# Gain.net
KiCad netlist of a schematic drawn in Altium Designer
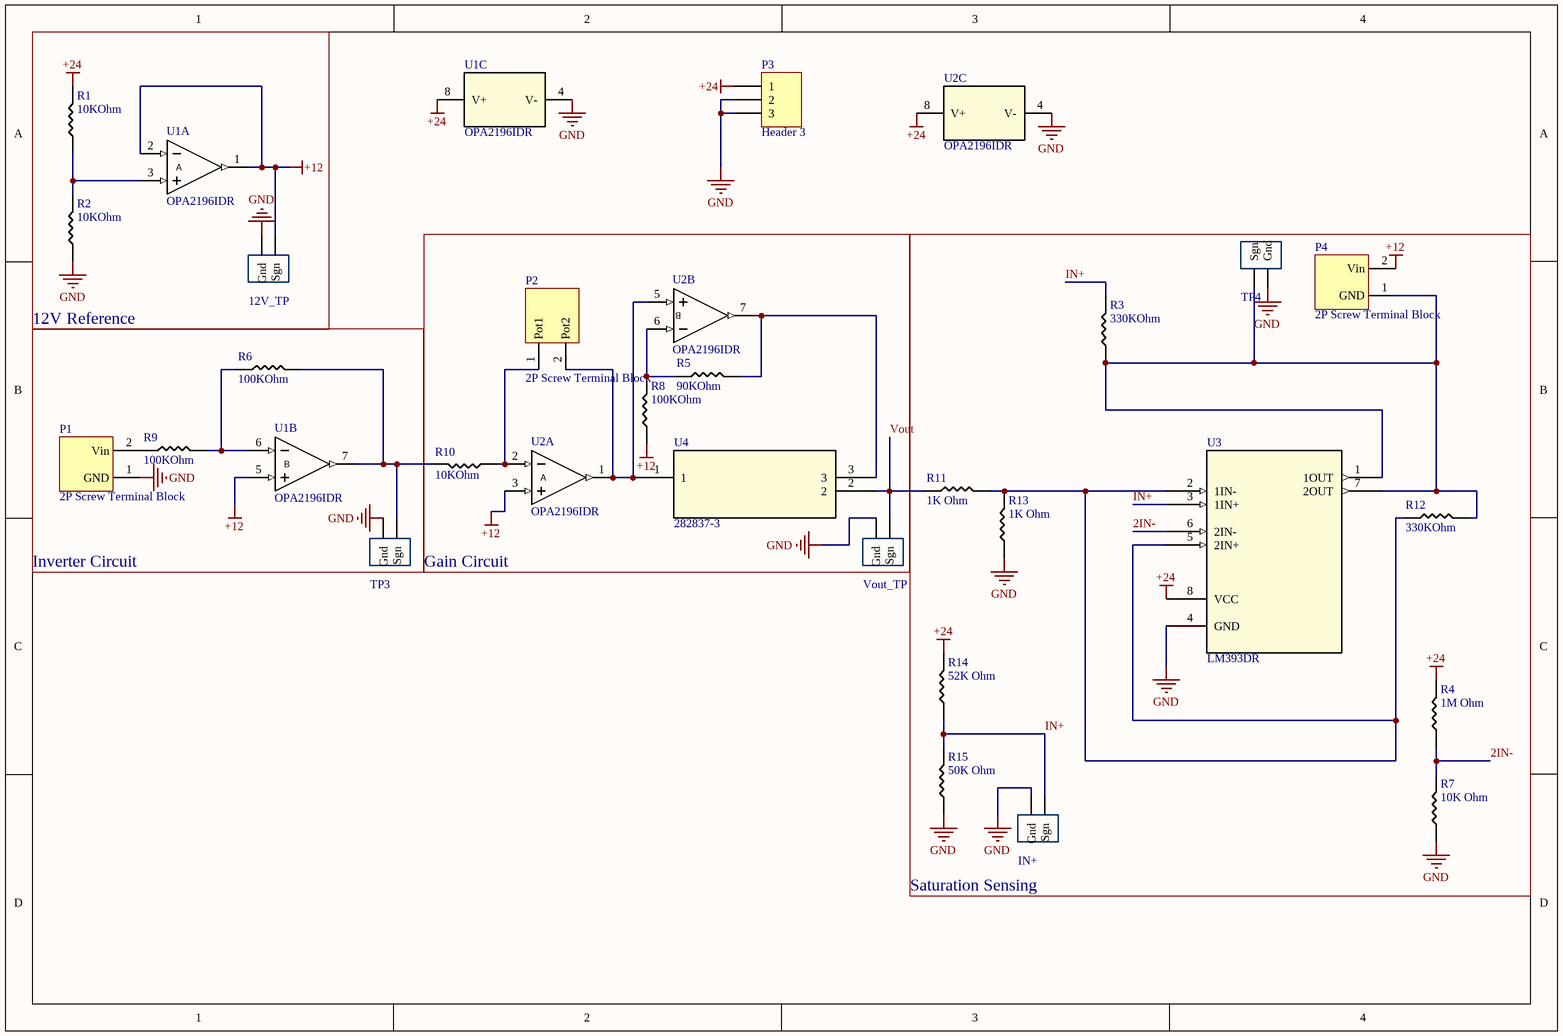
[diagram p0: Gain.SchDoc]

(export (version "E")
  (design (tool "Eeschema 10.0.6"))
  (components
    (comp (ref "12V_TP")
      (value "10x Probe TP")
      (footprint "TP10x_Probe")
      (description "Test Point 300 mil centers")
      (libsource (lib "") (part "TP_10x_Probe_1"))
    )
    (comp (ref "IN+")
      (value "10x Probe TP")
      (footprint "TP10x_Probe")
      (description "Test Point 300 mil centers")
      (libsource (lib "") (part "TP_10x_Probe_1"))
    )
    (comp (ref "P1")
      (value "2P Screw Terminal Block")
      (footprint "P_Terminal block 3.5mm-pitch")
      (description "Green Straight pin 3.5mm  pitch; P=3.5mm  Screw terminal ROHS")
      (fields (field (name "MFR PART #") "KF350-3.5-2P") (field (name "MANUFACTURER") "Cixi Kefa Elec"))
      (libsource (lib "") (part "P_Terminal block_1"))
    )
    (comp (ref "P2")
      (value "2P Screw Terminal Block")
      (footprint "P_Terminal block 3.5mm-pitch")
      (description "Green Straight pin 3.5mm  pitch; P=3.5mm  Screw terminal ROHS")
      (fields (field (name "MFR PART #") "KF350-3.5-2P") (field (name "MANUFACTURER") "Cixi Kefa Elec"))
      (libsource (lib "ECEN5730Lib_2023_05_DS") (part "P_Terminal block"))
    )
    (comp (ref "P3")
      (value "Header 3")
      (footprint "HDR1X3")
      (description "Header, 3-Pin")
      (fields (field (name "PUBLISHER") "Altium Limited"))
      (libsource (lib "Miscellaneous Connectors") (part "Header 3"))
    )
    (comp (ref "P4")
      (value "2P Screw Terminal Block")
      (footprint "P_Terminal block 3.5mm-pitch")
      (description "Green Straight pin 3.5mm  pitch; P=3.5mm  Screw terminal ROHS")
      (fields (field (name "MFR PART #") "KF350-3.5-2P") (field (name "MANUFACTURER") "Cixi Kefa Elec"))
      (libsource (lib "") (part "P_Terminal block_1"))
    )
    (comp (ref "R1")
      (value "10KOhm")
      (footprint "1206_Passive_Resitor")
      (description "10 kOhms ±5% 0.25W, 1/4W Chip Resistor 1206 (3216 Metric) Automotive AEC-Q200 Thick Film")
      (fields (field (name "MFR PART #") "RMCF1206FT10K0") (field (name "LCSC PART#") "C17902"))
      (libsource (lib "ECEN5730Lib_2023_05_DS") (part "R_10KOhm_1206"))
    )
    (comp (ref "R2")
      (value "10KOhm")
      (footprint "1206_Passive_Resitor")
      (description "10 kOhms ±5% 0.25W, 1/4W Chip Resistor 1206 (3216 Metric) Automotive AEC-Q200 Thick Film")
      (fields (field (name "MFR PART #") "RMCF1206FT10K0") (field (name "LCSC PART#") "C17902"))
      (libsource (lib "ECEN5730Lib_2023_05_DS") (part "R_10KOhm_1206"))
    )
    (comp (ref "R3")
      (value "330KOhm")
      (footprint "1206_Passive_Resitor")
      (description "CHIP RESISTOR - SURFACE MOUNT 300OHMS ±1% 1/4W 1206 ROHS")
      (fields (field (name "MFR PART #") "1206W4F3000T5E") (field (name "LCSC PART#") "C17887"))
      (libsource (lib "ECEN5730Lib_2023_05_DS") (part "R_300Ohm_1206"))
    )
    (comp (ref "R4")
      (value "1M Ohm")
      (footprint "1206_Passive_Resitor")
      (description "CHIP RESISTOR - SURFACE MOUNT 1KOHMS ±1% 1/4W 1206 ROHS")
      (fields (field (name "MFR PART #") "RNCP1206FTD1K00CT") (field (name "LCSC PART#") "C4410"))
      (libsource (lib "ECEN5730Lib_2023_05_DS") (part "R_1K_1206"))
    )
    (comp (ref "R5")
      (value "90KOhm")
      (footprint "1206_Passive_Resitor")
      (description "100kΩ ±1% 0.25W ±100ppm/℃ 1206 Chip Resistor - Surface Mount RoHS")
      (fields (field (name "LCSC PART#") "C17900") (field (name "MFR PART #") "1206W4F1003T5E"))
      (libsource (lib "ECEN5730Lib_2023_05_DS") (part "R_100KOhm_1206"))
    )
    (comp (ref "R6")
      (value "100KOhm")
      (footprint "1206_Passive_Resitor")
      (description "100kΩ ±1% 0.25W ±100ppm/℃ 1206 Chip Resistor - Surface Mount RoHS")
      (fields (field (name "LCSC PART#") "C17900") (field (name "MFR PART #") "1206W4F1003T5E"))
      (libsource (lib "ECEN5730Lib_2023_05_DS") (part "R_100KOhm_1206"))
    )
    (comp (ref "R7")
      (value "10K Ohm")
      (footprint "1206_Passive_Resitor")
      (description "CHIP RESISTOR - SURFACE MOUNT 1KOHMS ±1% 1/4W 1206 ROHS")
      (fields (field (name "MFR PART #") "RNCP1206FTD1K00CT") (field (name "LCSC PART#") "C4410"))
      (libsource (lib "ECEN5730Lib_2023_05_DS") (part "R_1K_1206"))
    )
    (comp (ref "R8")
      (value "100KOhm")
      (footprint "1206_Passive_Resitor")
      (description "100kΩ ±1% 0.25W ±100ppm/℃ 1206 Chip Resistor - Surface Mount RoHS")
      (fields (field (name "LCSC PART#") "C17900") (field (name "MFR PART #") "1206W4F1003T5E"))
      (libsource (lib "ECEN5730Lib_2023_05_DS") (part "R_100KOhm_1206"))
    )
    (comp (ref "R9")
      (value "100KOhm")
      (footprint "1206_Passive_Resitor")
      (description "100kΩ ±1% 0.25W ±100ppm/℃ 1206 Chip Resistor - Surface Mount RoHS")
      (fields (field (name "LCSC PART#") "C17900") (field (name "MFR PART #") "1206W4F1003T5E"))
      (libsource (lib "ECEN5730Lib_2023_05_DS") (part "R_100KOhm_1206"))
    )
    (comp (ref "R10")
      (value "10KOhm")
      (footprint "1206_Passive_Resitor")
      (description "10 kOhms ±5% 0.25W, 1/4W Chip Resistor 1206 (3216 Metric) Automotive AEC-Q200 Thick Film")
      (fields (field (name "MFR PART #") "RMCF1206FT10K0") (field (name "LCSC PART#") "C17902"))
      (libsource (lib "ECEN5730Lib_2023_05_DS") (part "R_10KOhm_1206"))
    )
    (comp (ref "R11")
      (value "1K Ohm")
      (footprint "1206_Passive_Resitor")
      (description "CHIP RESISTOR - SURFACE MOUNT 1KOHMS ±1% 1/4W 1206 ROHS")
      (fields (field (name "MFR PART #") "RNCP1206FTD1K00CT") (field (name "LCSC PART#") "C4410"))
      (libsource (lib "ECEN5730Lib_2023_05_DS") (part "R_1K_1206"))
    )
    (comp (ref "R12")
      (value "330KOhm")
      (footprint "1206_Passive_Resitor")
      (description "CHIP RESISTOR - SURFACE MOUNT 300OHMS ±1% 1/4W 1206 ROHS")
      (fields (field (name "MFR PART #") "1206W4F3000T5E") (field (name "LCSC PART#") "C17887"))
      (libsource (lib "ECEN5730Lib_2023_05_DS") (part "R_300Ohm_1206"))
    )
    (comp (ref "R13")
      (value "1K Ohm")
      (footprint "1206_Passive_Resitor")
      (description "CHIP RESISTOR - SURFACE MOUNT 1KOHMS ±1% 1/4W 1206 ROHS")
      (fields (field (name "MFR PART #") "RNCP1206FTD1K00CT") (field (name "LCSC PART#") "C4410"))
      (libsource (lib "ECEN5730Lib_2023_05_DS") (part "R_1K_1206"))
    )
    (comp (ref "R14")
      (value "52K Ohm")
      (footprint "1206_Passive_Resitor")
      (description "CHIP RESISTOR - SURFACE MOUNT 1KOHMS ±1% 1/4W 1206 ROHS")
      (fields (field (name "MFR PART #") "RNCP1206FTD1K00CT") (field (name "LCSC PART#") "C4410"))
      (libsource (lib "ECEN5730Lib_2023_05_DS") (part "R_1K_1206"))
    )
    (comp (ref "R15")
      (value "50K Ohm")
      (footprint "1206_Passive_Resitor")
      (description "CHIP RESISTOR - SURFACE MOUNT 1KOHMS ±1% 1/4W 1206 ROHS")
      (fields (field (name "MFR PART #") "RNCP1206FTD1K00CT") (field (name "LCSC PART#") "C4410"))
      (libsource (lib "ECEN5730Lib_2023_05_DS") (part "R_1K_1206"))
    )
    (comp (ref "TP3")
      (value "10x Probe TP")
      (footprint "TP10x_Probe")
      (description "Test Point 300 mil centers")
      (libsource (lib "") (part "TP_10x_Probe_1"))
    )
    (comp (ref "TP4")
      (value "10x Probe TP")
      (footprint "TP10x_Probe")
      (description "Test Point 300 mil centers")
      (libsource (lib "ECEN5730Lib_2023_05_DS") (part "TP_10x_Probe"))
    )
    (comp (ref "U1")
      (value "OPA2196IDR")
      (footprint "D0008A_N")
      (description "Dual, 36-V, low power, all-purpose amplifier with mux-friendly input 8-SOIC -40 to 125")
      (fields (field (name "COPYRIGHT") "Copyright (C) 2026 Ultra Librarian. All rights reserved."))
      (libsource (lib "Integrated_Library1") (part "OPA2196IDR"))
    )
    (comp (ref "U2")
      (value "OPA2196IDR")
      (footprint "D0008A_N")
      (description "Dual, 36-V, low power, all-purpose amplifier with mux-friendly input 8-SOIC -40 to 125")
      (fields (field (name "COPYRIGHT") "Copyright (C) 2026 Ultra Librarian. All rights reserved."))
      (libsource (lib "") (part "OPA2196IDR_1"))
    )
    (comp (ref "U3")
      (value "LM393DR")
      (footprint "D8")
      (description "Dual differential comparator, commercial grade 8-SOIC 0 to 70")
      (fields (field (name "COPYRIGHT") "Copyright (C) 2025 Ultra Librarian. All rights reserved."))
      (libsource (lib "LM393DR") (part "LM393DR"))
    )
    (comp (ref "U4")
      (value "282837-3")
      (footprint "282837-3_TYC")
      (description "TERMI-BLOK PCB MOUNT 3P")
      (fields (field (name "COPYRIGHT") "Copyright (C) 2025 Ultra Librarian. All rights reserved."))
      (libsource (lib "282837-3") (part "282837-3"))
    )
    (comp (ref "Vout_TP")
      (value "10x Probe TP")
      (footprint "TP10x_Probe")
      (description "Test Point 300 mil centers")
      (libsource (lib "") (part "TP_10x_Probe_1"))
    )
  )
  (nets
    (net (code "1") (name "+12") (class "Default")
      (node (ref "12V_TP") (pin "1") (pinfunction "Sgn_1") (pintype "passive"))
      (node (ref "P4") (pin "2") (pinfunction "Vin_2") (pintype "passive"))
      (node (ref "R8") (pin "1") (pinfunction "1_1") (pintype "passive"))
      (node (ref "U1") (pin "1") (pinfunction "OUT_1") (pintype "output"))
      (node (ref "U1") (pin "2") (pinfunction "IN-_2") (pintype "input"))
      (node (ref "U1") (pin "5") (pinfunction "IN+_5") (pintype "input"))
      (node (ref "U2") (pin "3") (pinfunction "IN+_3") (pintype "input"))
    )
    (net (code "2") (name "+24") (class "Default")
      (node (ref "P3") (pin "1") (pinfunction "1_1") (pintype "passive"))
      (node (ref "R1") (pin "2") (pinfunction "2_2") (pintype "passive"))
      (node (ref "R14") (pin "2") (pinfunction "2_2") (pintype "passive"))
      (node (ref "R4") (pin "2") (pinfunction "2_2") (pintype "passive"))
      (node (ref "U1") (pin "8") (pinfunction "V+_8") (pintype "power_in"))
      (node (ref "U2") (pin "8") (pinfunction "V+_8") (pintype "power_in"))
      (node (ref "U3") (pin "8") (pinfunction "VCC_8") (pintype "power_in"))
    )
    (net (code "3") (name "/2IN-") (class "Default")
      (node (ref "R4") (pin "1") (pinfunction "1_1") (pintype "passive"))
      (node (ref "R7") (pin "2") (pinfunction "2_2") (pintype "passive"))
      (node (ref "U3") (pin "6") (pinfunction "2IN-_6") (pintype "input"))
    )
    (net (code "4") (name "/IN+") (class "Default")
      (node (ref "IN+") (pin "1") (pinfunction "Sgn_1") (pintype "passive"))
      (node (ref "R14") (pin "1") (pinfunction "1_1") (pintype "passive"))
      (node (ref "R15") (pin "2") (pinfunction "2_2") (pintype "passive"))
      (node (ref "R3") (pin "2") (pinfunction "2_2") (pintype "passive"))
      (node (ref "U3") (pin "3") (pinfunction "1IN+_3") (pintype "input"))
    )
    (net (code "5") (name "/Vout") (class "Default")
      (node (ref "R11") (pin "1") (pinfunction "1_1") (pintype "passive"))
      (node (ref "U4") (pin "2") (pinfunction "2_2") (pintype "passive"))
      (node (ref "Vout_TP") (pin "1") (pinfunction "Sgn_1") (pintype "passive"))
    )
    (net (code "6") (name "GND") (class "Default")
      (node (ref "12V_TP") (pin "2") (pinfunction "Gnd_2") (pintype "passive"))
      (node (ref "IN+") (pin "2") (pinfunction "Gnd_2") (pintype "passive"))
      (node (ref "P1") (pin "1") (pinfunction "GND_1") (pintype "passive"))
      (node (ref "P3") (pin "2") (pinfunction "2_2") (pintype "passive"))
      (node (ref "P3") (pin "3") (pinfunction "3_3") (pintype "passive"))
      (node (ref "R13") (pin "1") (pinfunction "1_1") (pintype "passive"))
      (node (ref "R15") (pin "1") (pinfunction "1_1") (pintype "passive"))
      (node (ref "R2") (pin "1") (pinfunction "1_1") (pintype "passive"))
      (node (ref "R7") (pin "1") (pinfunction "1_1") (pintype "passive"))
      (node (ref "TP3") (pin "2") (pinfunction "Gnd_2") (pintype "passive"))
      (node (ref "TP4") (pin "2") (pinfunction "Gnd_2") (pintype "passive"))
      (node (ref "U1") (pin "4") (pinfunction "V-_4") (pintype "power_in"))
      (node (ref "U2") (pin "4") (pinfunction "V-_4") (pintype "power_in"))
      (node (ref "U3") (pin "4") (pinfunction "GND_4") (pintype "power_in"))
      (node (ref "Vout_TP") (pin "2") (pinfunction "Gnd_2") (pintype "passive"))
    )
    (net (code "7") (name "Net-(P1-Vin)") (class "Default")
      (node (ref "P1") (pin "2") (pinfunction "Vin_2") (pintype "passive"))
      (node (ref "R9") (pin "1") (pinfunction "1_1") (pintype "passive"))
    )
    (net (code "8") (name "Net-(P2-Pot1)") (class "Default")
      (node (ref "P2") (pin "1") (pinfunction "Pot1_1") (pintype "passive"))
      (node (ref "R10") (pin "1") (pinfunction "1_1") (pintype "passive"))
      (node (ref "U2") (pin "2") (pinfunction "IN-_2") (pintype "input"))
    )
    (net (code "9") (name "Net-(P2-Pot2)") (class "Default")
      (node (ref "P2") (pin "2") (pinfunction "Pot2_2") (pintype "passive"))
      (node (ref "U2") (pin "1") (pinfunction "OUT_1") (pintype "output"))
      (node (ref "U2") (pin "5") (pinfunction "IN+_5") (pintype "input"))
      (node (ref "U4") (pin "1") (pinfunction "1_1") (pintype "passive"))
    )
    (net (code "10") (name "Net-(P4-GND)") (class "Default")
      (node (ref "P4") (pin "1") (pinfunction "GND_1") (pintype "passive"))
      (node (ref "R12") (pin "2") (pinfunction "2_2") (pintype "passive"))
      (node (ref "R3") (pin "1") (pinfunction "1_1") (pintype "passive"))
      (node (ref "TP4") (pin "1") (pinfunction "Sgn_1") (pintype "passive"))
      (node (ref "U3") (pin "1") (pinfunction "1OUT_1") (pintype "output"))
      (node (ref "U3") (pin "7") (pinfunction "2OUT_7") (pintype "output"))
    )
    (net (code "11") (name "Net-(TP3-Sgn)") (class "Default")
      (node (ref "R10") (pin "2") (pinfunction "2_2") (pintype "passive"))
      (node (ref "R6") (pin "2") (pinfunction "2_2") (pintype "passive"))
      (node (ref "TP3") (pin "1") (pinfunction "Sgn_1") (pintype "passive"))
      (node (ref "U1") (pin "7") (pinfunction "OUT_7") (pintype "output"))
    )
    (net (code "12") (name "Net-(U1A-IN+)") (class "Default")
      (node (ref "R1") (pin "1") (pinfunction "1_1") (pintype "passive"))
      (node (ref "R2") (pin "2") (pinfunction "2_2") (pintype "passive"))
      (node (ref "U1") (pin "3") (pinfunction "IN+_3") (pintype "input"))
    )
    (net (code "13") (name "Net-(U1B-IN-)") (class "Default")
      (node (ref "R6") (pin "1") (pinfunction "1_1") (pintype "passive"))
      (node (ref "R9") (pin "2") (pinfunction "2_2") (pintype "passive"))
      (node (ref "U1") (pin "6") (pinfunction "IN-_6") (pintype "input"))
    )
    (net (code "14") (name "Net-(U2B-IN-)") (class "Default")
      (node (ref "R5") (pin "1") (pinfunction "1_1") (pintype "passive"))
      (node (ref "R8") (pin "2") (pinfunction "2_2") (pintype "passive"))
      (node (ref "U2") (pin "6") (pinfunction "IN-_6") (pintype "input"))
    )
    (net (code "15") (name "Net-(U2B-OUT)") (class "Default")
      (node (ref "R5") (pin "2") (pinfunction "2_2") (pintype "passive"))
      (node (ref "U2") (pin "7") (pinfunction "OUT_7") (pintype "output"))
      (node (ref "U4") (pin "3") (pinfunction "3_3") (pintype "passive"))
    )
    (net (code "16") (name "Net-(U3-1IN-)") (class "Default")
      (node (ref "R11") (pin "2") (pinfunction "2_2") (pintype "passive"))
      (node (ref "R12") (pin "1") (pinfunction "1_1") (pintype "passive"))
      (node (ref "R13") (pin "2") (pinfunction "2_2") (pintype "passive"))
      (node (ref "U3") (pin "2") (pinfunction "1IN-_2") (pintype "input"))
      (node (ref "U3") (pin "5") (pinfunction "2IN+_5") (pintype "input"))
    )
  )
)
